# Power_Supply.net
KiCad netlist of a schematic drawn in Altium Designer
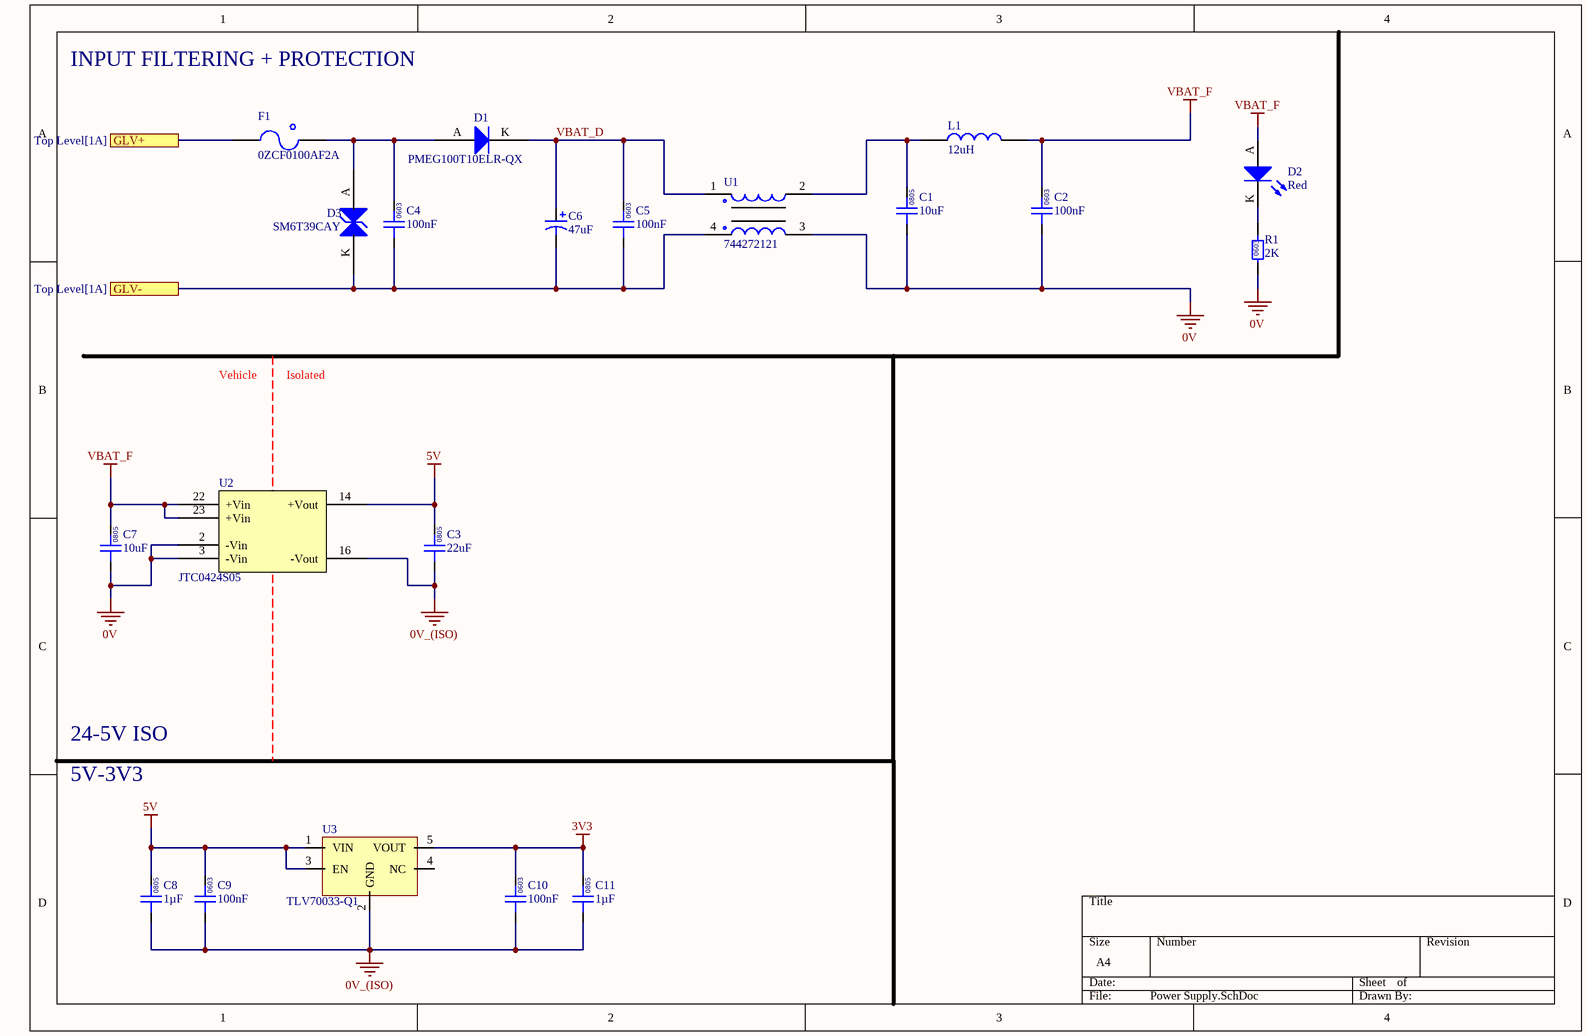
[diagram p0: Power Supply.SchDoc]

(export (version "E")
  (design (tool "Eeschema 10.0.6"))
  (components
    (comp (ref "C1")
      (value "10uF")
      (footprint "0805")
      (fields
        (field (name "PART NUMBER") "GRM21BR6YA106KE43L")
        (field (name "MANUFACTURER") "muRata")
        (field (name "TOLERANCE") "10%")
      )
      (libsource (lib "ts_standard_library") (part "Capacitor 0805"))
    )
    (comp (ref "C2")
      (value "100nF")
      (footprint "0603")
      (fields
        (field (name "PART NUMBER") "GCM188L81H104KA57D")
        (field (name "MANUFACTURER") "muRata")
        (field (name "TOLERANCE") "±10%")
      )
      (libsource (lib "ts_standard_library") (part "Capacitor 0603"))
    )
    (comp (ref "C3")
      (value "22uF")
      (footprint "0805")
      (fields
        (field (name "PART NUMBER") "GRM21BR61A226ME51L")
        (field (name "MANUFACTURER") "muRata")
        (field (name "TOLERANCE") "20%")
      )
      (libsource (lib "ts_standard_library") (part "Capacitor 0805"))
    )
    (comp (ref "C4")
      (value "100nF")
      (footprint "0603")
      (fields
        (field (name "PART NUMBER") "GCM188L81H104KA57D")
        (field (name "MANUFACTURER") "muRata")
        (field (name "TOLERANCE") "±10%")
      )
      (libsource (lib "ts_standard_library") (part "Capacitor 0603"))
    )
    (comp (ref "C5")
      (value "100nF")
      (footprint "0603")
      (fields
        (field (name "PART NUMBER") "GCM188L81H104KA57D")
        (field (name "MANUFACTURER") "muRata")
        (field (name "TOLERANCE") "±10%")
      )
      (libsource (lib "ts_standard_library") (part "Capacitor 0603"))
    )
    (comp (ref "C6")
      (value "47uF")
      (footprint "CHEMI-CON ELCO")
      (fields (field (name "PART NUMBER") "HHXA350ARA470MF61G"))
      (libsource (lib "ts_standard_library") (part "Capacitor (Polarised)"))
    )
    (comp (ref "C7")
      (value "10uF")
      (footprint "0805")
      (fields
        (field (name "PART NUMBER") "GRM21BR6YA106KE43L")
        (field (name "MANUFACTURER") "muRata")
        (field (name "TOLERANCE") "10%")
      )
      (libsource (lib "ts_standard_library") (part "Capacitor 0805"))
    )
    (comp (ref "C8")
      (value "1µF")
      (footprint "0805")
      (fields
        (field (name "PART NUMBER") "GCM21BR71H105KA03L")
        (field (name "MANUFACTURER") "muRata")
        (field (name "TOLERANCE") "±10%")
      )
      (libsource (lib "ts_standard_library") (part "Capacitor 0805"))
    )
    (comp (ref "C9")
      (value "100nF")
      (footprint "0603")
      (fields
        (field (name "PART NUMBER") "GCM188L81H104KA57D")
        (field (name "MANUFACTURER") "muRata")
        (field (name "TOLERANCE") "±10%")
      )
      (libsource (lib "ts_standard_library") (part "Capacitor 0603"))
    )
    (comp (ref "C10")
      (value "100nF")
      (footprint "0603")
      (fields
        (field (name "PART NUMBER") "GCM188L81H104KA57D")
        (field (name "MANUFACTURER") "muRata")
        (field (name "TOLERANCE") "±10%")
      )
      (libsource (lib "ts_standard_library") (part "Capacitor 0603"))
    )
    (comp (ref "C11")
      (value "1µF")
      (footprint "0805")
      (fields
        (field (name "PART NUMBER") "GCM21BR71H105KA03L")
        (field (name "MANUFACTURER") "muRata")
        (field (name "TOLERANCE") "±10%")
      )
      (libsource (lib "ts_standard_library") (part "Capacitor 0805"))
    )
    (comp (ref "D1")
      (value "PMEG100T10ELR-QX")
      (footprint "SODFL350X110-2N")
      (description "Diode 100 V 1A Surface Mount SOD-123W")
      (libsource (lib "Team Swinburne") (part "PMEG100T10ELR-QX"))
    )
    (comp (ref "D2")
      (value "Red")
      (footprint "0805 LED")
      (description "Red LED Indication - Discrete 1.75V 0805 (2012 Metric)")
      (fields (field (name "PART NUMBER") "SML-210LTT86") (field (name "MANUFACTURER") "ROHM Semiconductor"))
      (libsource (lib "ts_standard_library") (part "LED"))
    )
    (comp (ref "D3")
      (value "SM6T39CAY")
      (footprint "SM6T39CAY-Footprint-1")
      (description "TVS Diode Single Bi-Dir 33.3V 600W Automotive 2-Pin SMB T/R / TVS DIODE 33.3VWM 69.7VC SMB")
      (libsource (lib "Team Swinburne") (part "SM6T39CAY-Symbol"))
    )
    (comp (ref "F1")
      (value "0ZCF0100AF2A")
      (footprint "2920")
      (description "PTC RESET FUSE 60V 1A 292")
      (fields
        (field (name "MANUFACTURER") "Littelfuse Inc.")
        (field (name "DIGIKEY PART NUMBER") "507-2070-1-ND")
      )
      (libsource (lib "ts_standard_library") (part "PTC Fuse"))
    )
    (comp (ref "L1")
      (value "12uH")
      (footprint "1812")
      (fields
        (field (name "PART NUMBER") "RLS-126")
        (field (name "MANUFACTURER") "Recom")
        (field (name "TOLERANCE") "0.2")
      )
      (libsource (lib "ts_standard_library") (part "Inductor"))
    )
    (comp (ref "R1")
      (value "2K")
      (footprint "0603")
      (fields
        (field (name "PART NUMBER") "RC0603FR-072KL")
        (field (name "MANUFACTURER") "YAGEO")
        (field (name "TOLERANCE") "0.01")
      )
      (libsource (lib "ts_standard_library") (part "Resistor 0603"))
    )
    (comp (ref "U1")
      (value "744272121")
      (footprint "Wurth 4-PC Pad")
      (fields
        (field (name "MANUFACTURER") "Wurth Electronics Inc")
        (field (name "DIGIKEY PART NUMBER") "732-1489-1-ND")
      )
      (libsource (lib "ts_standard_library") (part "CM Choke"))
    )
    (comp (ref "U2")
      (value "JTC0424S05")
      (footprint "24-DIP Module, 7 Leads")
      (description "DC DC CONVERTER 5V 4W")
      (fields (field (name "MANUFACTURER") "XP Power") (field (name "DIGIKEY PART NUMBER") "JTC0424S05-ND"))
      (libsource (lib "ts_20-standard-library") (part "JTC0424S05"))
    )
    (comp (ref "U3")
      (value "TLV70033-Q1")
      (footprint "TI SOT-23-5")
      (description "IC REG LINEAR 3.3V 200MA SOT23-5")
      (fields
        (field (name "MANUFACTURER") "Texas Instruments")
        (field (name "DIGIKEY PART NUMBER") "296-27780-1-ND")
      )
      (libsource (lib "ts_standard_library") (part "TLV70033-Q1"))
    )
  )
  (nets
    (net (code "1") (name "/GLV+") (class "Default")
      (node (ref "F1") (pin "1") (pinfunction "1_1") (pintype "passive"))
    )
    (net (code "2") (name "/GLV-") (class "Default")
      (node (ref "C4") (pin "1") (pinfunction "1_1") (pintype "passive"))
      (node (ref "C5") (pin "1") (pinfunction "1_1") (pintype "passive"))
      (node (ref "C6") (pin "1") (pinfunction "1_1") (pintype "passive"))
      (node (ref "D3") (pin "K") (pintype "passive"))
      (node (ref "U1") (pin "4") (pinfunction "4_4") (pintype "passive"))
    )
    (net (code "3") (name "/VBAT_D") (class "Default")
      (node (ref "C5") (pin "2") (pinfunction "2_2") (pintype "passive"))
      (node (ref "C6") (pin "2") (pinfunction "2_2") (pintype "passive"))
      (node (ref "D1") (pin "K") (pintype "passive"))
      (node (ref "U1") (pin "1") (pinfunction "1_1") (pintype "passive"))
    )
    (net (code "4") (name "0V") (class "Default")
      (node (ref "C1") (pin "1") (pinfunction "1_1") (pintype "passive"))
      (node (ref "C2") (pin "1") (pinfunction "1_1") (pintype "passive"))
      (node (ref "C7") (pin "1") (pinfunction "1_1") (pintype "passive"))
      (node (ref "R1") (pin "1") (pinfunction "1_1") (pintype "passive"))
      (node (ref "U1") (pin "3") (pinfunction "3_3") (pintype "power_in"))
      (node (ref "U2") (pin "2") (pinfunction "-Vin_2") (pintype "passive"))
      (node (ref "U2") (pin "3") (pinfunction "-Vin_3") (pintype "passive"))
    )
    (net (code "5") (name "0V_(ISO)") (class "Default")
      (node (ref "C10") (pin "1") (pinfunction "1_1") (pintype "passive"))
      (node (ref "C11") (pin "1") (pinfunction "1_1") (pintype "passive"))
      (node (ref "C3") (pin "1") (pinfunction "1_1") (pintype "passive"))
      (node (ref "C8") (pin "1") (pinfunction "1_1") (pintype "passive"))
      (node (ref "C9") (pin "1") (pinfunction "1_1") (pintype "passive"))
      (node (ref "U2") (pin "16") (pinfunction "-Vout_16") (pintype "passive"))
      (node (ref "U3") (pin "2") (pinfunction "GND_2") (pintype "passive"))
    )
    (net (code "6") (name "3V3") (class "Default")
      (node (ref "C10") (pin "2") (pinfunction "2_2") (pintype "passive"))
      (node (ref "C11") (pin "2") (pinfunction "2_2") (pintype "passive"))
      (node (ref "U3") (pin "5") (pinfunction "VOUT_5") (pintype "passive"))
    )
    (net (code "7") (name "5V") (class "Default")
      (node (ref "C3") (pin "2") (pinfunction "2_2") (pintype "passive"))
      (node (ref "C8") (pin "2") (pinfunction "2_2") (pintype "passive"))
      (node (ref "C9") (pin "2") (pinfunction "2_2") (pintype "passive"))
      (node (ref "U2") (pin "14") (pinfunction "+Vout_14") (pintype "passive"))
      (node (ref "U3") (pin "1") (pinfunction "VIN_1") (pintype "passive"))
      (node (ref "U3") (pin "3") (pinfunction "EN_3") (pintype "passive"))
    )
    (net (code "8") (name "Net-(C1-Pad2)") (class "Default")
      (node (ref "C1") (pin "2") (pinfunction "2_2") (pintype "passive"))
      (node (ref "L1") (pin "2") (pinfunction "2_2") (pintype "passive"))
      (node (ref "U1") (pin "2") (pinfunction "2_2") (pintype "passive"))
    )
    (net (code "9") (name "Net-(C4-Pad2)") (class "Default")
      (node (ref "C4") (pin "2") (pinfunction "2_2") (pintype "passive"))
      (node (ref "D1") (pin "A") (pintype "passive"))
      (node (ref "D3") (pin "A") (pintype "passive"))
      (node (ref "F1") (pin "2") (pinfunction "2_2") (pintype "passive"))
    )
    (net (code "10") (name "Net-(D2-PadK)") (class "Default")
      (node (ref "D2") (pin "K") (pinfunction "K_K") (pintype "passive"))
      (node (ref "R1") (pin "2") (pinfunction "2_2") (pintype "passive"))
    )
    (net (code "11") (name "VBAT_F") (class "Default")
      (node (ref "C2") (pin "2") (pinfunction "2_2") (pintype "passive"))
      (node (ref "C7") (pin "2") (pinfunction "2_2") (pintype "passive"))
      (node (ref "D2") (pin "A") (pinfunction "A_A") (pintype "passive"))
      (node (ref "L1") (pin "1") (pinfunction "1_1") (pintype "passive"))
      (node (ref "U2") (pin "22") (pinfunction "+Vin_22") (pintype "passive"))
      (node (ref "U2") (pin "23") (pinfunction "+Vin_23") (pintype "passive"))
    )
    (net (code "12") (name "unconnected-(U3-NC-Pad4)") (class "Default")
      (node (ref "U3") (pin "4") (pinfunction "NC_4") (pintype "passive"))
    )
  )
)
